# RTD_circuit.net
KiCad netlist of a schematic drawn in EAGLE
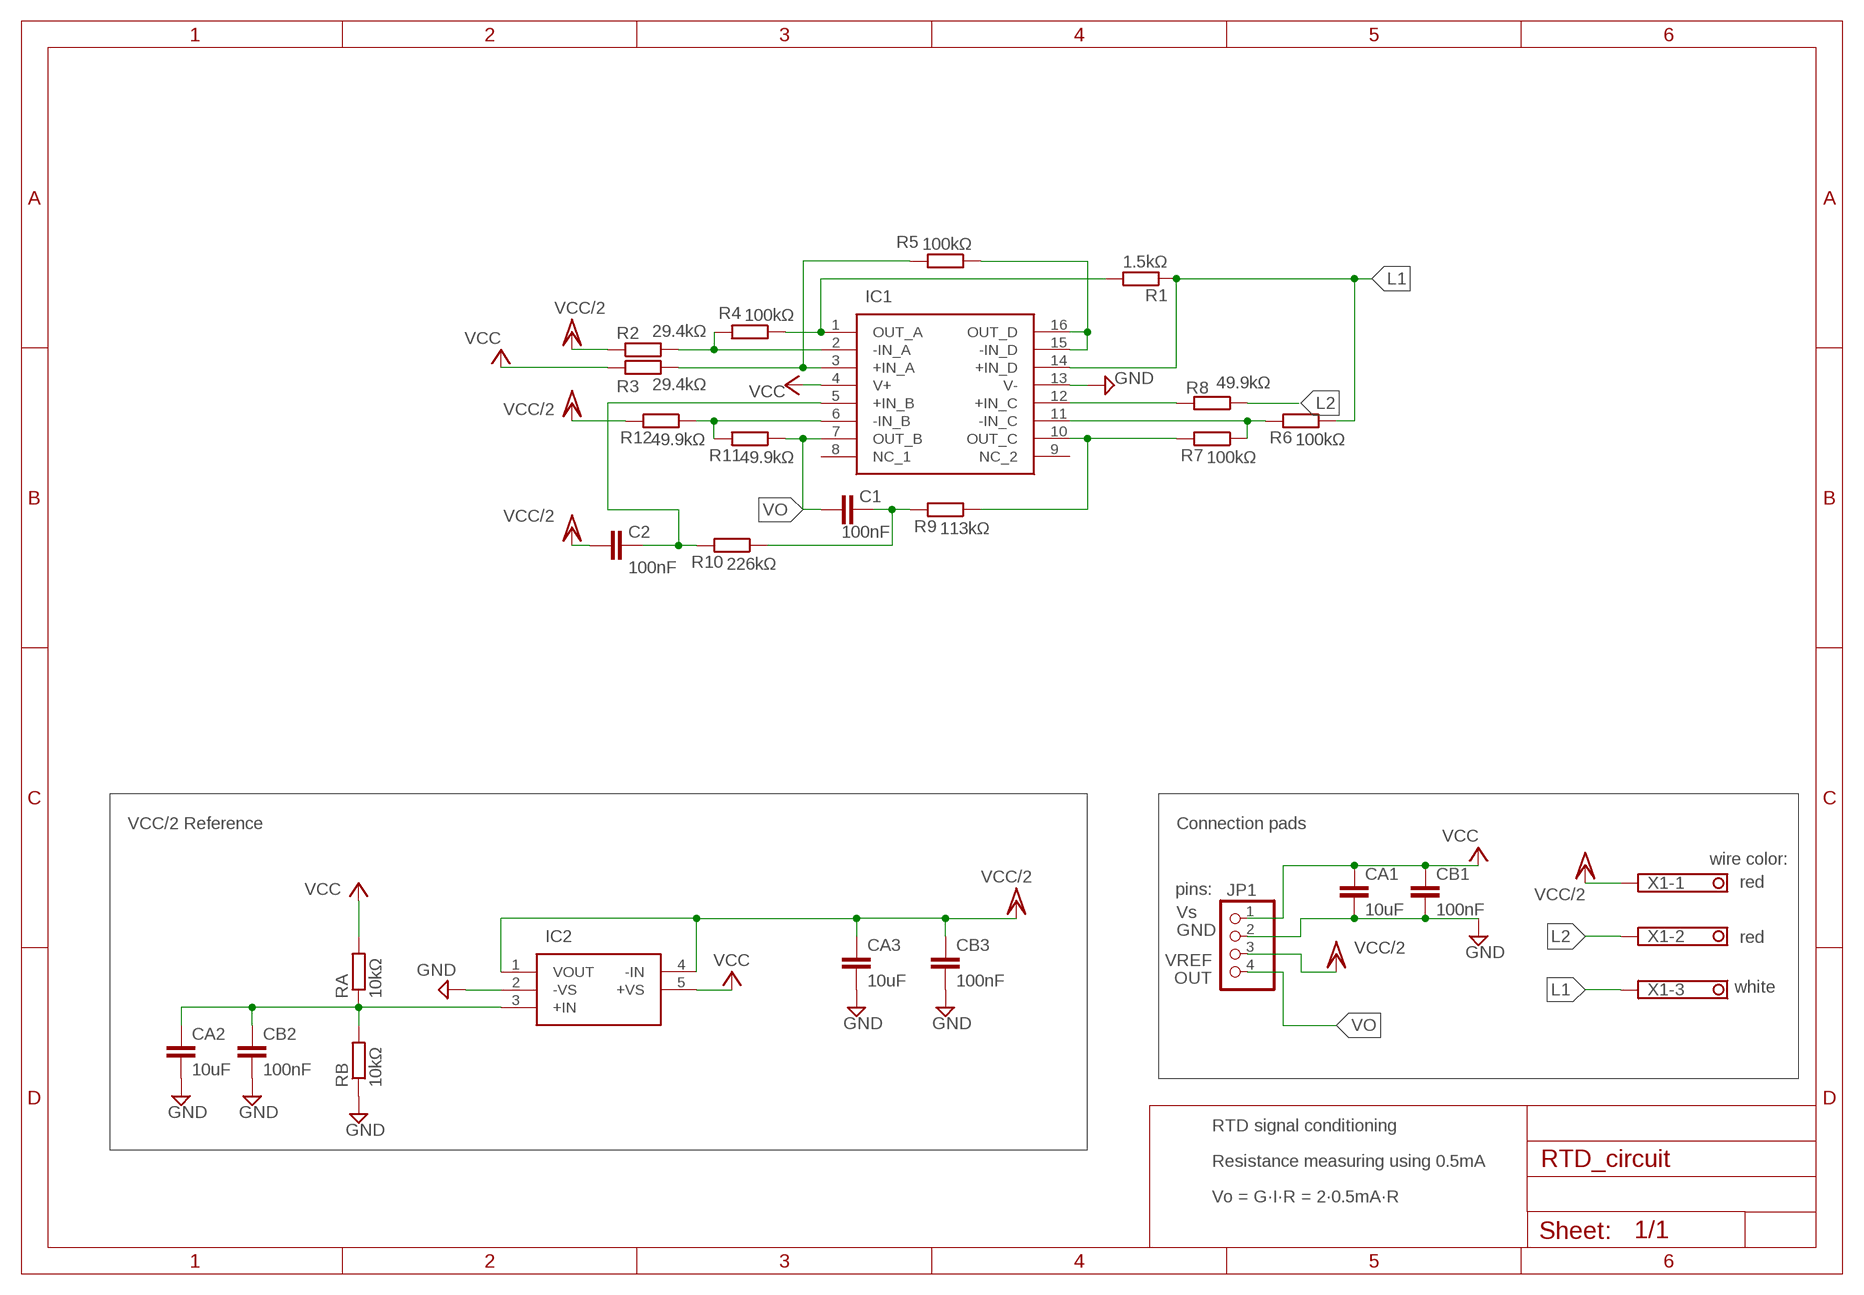
[diagram p0: schematic, sheet 1]

(export (version "E")
  (design (tool "Eeschema 10.0.6"))
  (components
    (comp (ref "C1")
      (value "100nF")
      (footprint "eagle-import:C0603")
      (libsource (lib "eagle-import") (part "C-EUC0603"))
    )
    (comp (ref "C2")
      (value "100nF")
      (footprint "eagle-import:C0603")
      (libsource (lib "eagle-import") (part "C-EUC0603"))
    )
    (comp (ref "CA1")
      (value "10uF")
      (footprint "eagle-import:C0603")
      (libsource (lib "eagle-import") (part "C-EUC0603"))
    )
    (comp (ref "CA2")
      (value "10uF")
      (footprint "eagle-import:C0603")
      (libsource (lib "eagle-import") (part "C-EUC0603"))
    )
    (comp (ref "CA3")
      (value "10uF")
      (footprint "eagle-import:C0603")
      (libsource (lib "eagle-import") (part "C-EUC0603"))
    )
    (comp (ref "CB1")
      (value "100nF")
      (footprint "eagle-import:C0603")
      (libsource (lib "eagle-import") (part "C-EUC0603"))
    )
    (comp (ref "CB2")
      (value "100nF")
      (footprint "eagle-import:C0603")
      (libsource (lib "eagle-import") (part "C-EUC0603"))
    )
    (comp (ref "CB3")
      (value "100nF")
      (footprint "eagle-import:C0603")
      (libsource (lib "eagle-import") (part "C-EUC0603"))
    )
    (comp (ref "IC1")
      (value "LT1079SW#PBF")
      (footprint "eagle-import:SOIC127P1032X264-16N")
      (fields (field (name "MOUSER_PART_NUMBER") "584-LT1079SW#PBF"))
      (libsource (lib "eagle-import") (part "LT1079SW#PBF"))
    )
    (comp (ref "IC2")
      (value "AD8031ARTZ-R2")
      (footprint "eagle-import:SOT95P280X145-5N")
      (fields (field (name "MOUSER_PART_NUMBER") "584-AD8031ARTZ-R2"))
      (libsource (lib "eagle-import") (part "AD8031ARTZ-R2"))
    )
    (comp (ref "JP1")
      (value "PINHD-1X4")
      (footprint "eagle-import:1X04")
      (libsource (lib "eagle-import") (part "PINHD-1X4"))
    )
    (comp (ref "R1")
      (value "1.5kΩ")
      (footprint "eagle-import:R0603")
      (libsource (lib "eagle-import") (part "R-EU_R0603"))
    )
    (comp (ref "R2")
      (value "29.4kΩ")
      (footprint "eagle-import:R0603")
      (libsource (lib "eagle-import") (part "R-EU_R0603"))
    )
    (comp (ref "R3")
      (value "29.4kΩ")
      (footprint "eagle-import:R0603")
      (libsource (lib "eagle-import") (part "R-EU_R0603"))
    )
    (comp (ref "R4")
      (value "100kΩ")
      (footprint "eagle-import:R0603")
      (libsource (lib "eagle-import") (part "R-EU_R0603"))
    )
    (comp (ref "R5")
      (value "100kΩ")
      (footprint "eagle-import:R0603")
      (libsource (lib "eagle-import") (part "R-EU_R0603"))
    )
    (comp (ref "R6")
      (value "100kΩ")
      (footprint "eagle-import:R0603")
      (libsource (lib "eagle-import") (part "R-EU_R0603"))
    )
    (comp (ref "R7")
      (value "100kΩ")
      (footprint "eagle-import:R0603")
      (libsource (lib "eagle-import") (part "R-EU_R0603"))
    )
    (comp (ref "R8")
      (value "49.9kΩ")
      (footprint "eagle-import:R0603")
      (libsource (lib "eagle-import") (part "R-EU_R0603"))
    )
    (comp (ref "R9")
      (value "113kΩ")
      (footprint "eagle-import:R0603")
      (libsource (lib "eagle-import") (part "R-EU_R0603"))
    )
    (comp (ref "R10")
      (value "226kΩ")
      (footprint "eagle-import:R0603")
      (libsource (lib "eagle-import") (part "R-EU_R0603"))
    )
    (comp (ref "R11")
      (value "49.9kΩ")
      (footprint "eagle-import:R0603")
      (libsource (lib "eagle-import") (part "R-EU_R0603"))
    )
    (comp (ref "R12")
      (value "49.9kΩ")
      (footprint "eagle-import:R0603")
      (libsource (lib "eagle-import") (part "R-EU_R0603"))
    )
    (comp (ref "RA")
      (value "10kΩ")
      (footprint "eagle-import:R0603")
      (libsource (lib "eagle-import") (part "R-EU_R0603"))
    )
    (comp (ref "RB")
      (value "10kΩ")
      (footprint "eagle-import:R0603")
      (libsource (lib "eagle-import") (part "R-EU_R0603"))
    )
    (comp (ref "X1")
      (value "1751251")
      (footprint "eagle-import:1751251")
      (libsource (lib "eagle-import") (part "1751251"))
    )
  )
  (nets
    (net (code "1") (name "GND") (class "Default")
      (node (ref "CA1") (pin "2") (pinfunction "2_2") (pintype "passive"))
      (node (ref "CA2") (pin "2") (pinfunction "2_2") (pintype "passive"))
      (node (ref "CA3") (pin "2") (pinfunction "2_2") (pintype "passive"))
      (node (ref "CB1") (pin "2") (pinfunction "2_2") (pintype "passive"))
      (node (ref "CB2") (pin "2") (pinfunction "2_2") (pintype "passive"))
      (node (ref "CB3") (pin "2") (pinfunction "2_2") (pintype "passive"))
      (node (ref "IC1") (pin "13") (pinfunction "V-_13") (pintype "bidirectional"))
      (node (ref "IC2") (pin "2") (pinfunction "-VS_2") (pintype "bidirectional"))
      (node (ref "JP1") (pin "2") (pinfunction "2_2") (pintype "passive"))
      (node (ref "RB") (pin "1") (pinfunction "1_1") (pintype "passive"))
    )
    (net (code "2") (name "L1") (class "Default")
      (node (ref "IC1") (pin "14") (pinfunction "+IN_D_14") (pintype "bidirectional"))
      (node (ref "R1") (pin "1") (pinfunction "1_1") (pintype "passive"))
      (node (ref "R6") (pin "1") (pinfunction "1_1") (pintype "passive"))
      (node (ref "X1") (pin "3") (pinfunction "K_3") (pintype "passive"))
    )
    (net (code "3") (name "L2") (class "Default")
      (node (ref "R8") (pin "1") (pinfunction "1_1") (pintype "passive"))
      (node (ref "X1") (pin "2") (pinfunction "K_2") (pintype "passive"))
    )
    (net (code "4") (name "Net-(C1-Pad1)") (class "Default")
      (node (ref "C1") (pin "1") (pinfunction "1_1") (pintype "passive"))
      (node (ref "R10") (pin "1") (pinfunction "1_1") (pintype "passive"))
      (node (ref "R9") (pin "2") (pinfunction "2_2") (pintype "passive"))
    )
    (net (code "5") (name "Net-(IC1-+IN_A)") (class "Default")
      (node (ref "IC1") (pin "3") (pinfunction "+IN_A_3") (pintype "bidirectional"))
      (node (ref "R3") (pin "2") (pinfunction "2_2") (pintype "passive"))
      (node (ref "R5") (pin "2") (pinfunction "2_2") (pintype "passive"))
    )
    (net (code "6") (name "Net-(IC1-+IN_B)") (class "Default")
      (node (ref "C2") (pin "1") (pinfunction "1_1") (pintype "passive"))
      (node (ref "IC1") (pin "5") (pinfunction "+IN_B_5") (pintype "bidirectional"))
      (node (ref "R10") (pin "2") (pinfunction "2_2") (pintype "passive"))
    )
    (net (code "7") (name "Net-(IC1-+IN_C)") (class "Default")
      (node (ref "IC1") (pin "12") (pinfunction "+IN_C_12") (pintype "bidirectional"))
      (node (ref "R8") (pin "2") (pinfunction "2_2") (pintype "passive"))
    )
    (net (code "8") (name "Net-(IC1--IN_A)") (class "Default")
      (node (ref "IC1") (pin "2") (pinfunction "-IN_A_2") (pintype "bidirectional"))
      (node (ref "R2") (pin "2") (pinfunction "2_2") (pintype "passive"))
      (node (ref "R4") (pin "2") (pinfunction "2_2") (pintype "passive"))
    )
    (net (code "9") (name "Net-(IC1--IN_B)") (class "Default")
      (node (ref "IC1") (pin "6") (pinfunction "-IN_B_6") (pintype "bidirectional"))
      (node (ref "R11") (pin "2") (pinfunction "2_2") (pintype "passive"))
      (node (ref "R12") (pin "1") (pinfunction "1_1") (pintype "passive"))
    )
    (net (code "10") (name "Net-(IC1--IN_C)") (class "Default")
      (node (ref "IC1") (pin "11") (pinfunction "-IN_C_11") (pintype "bidirectional"))
      (node (ref "R6") (pin "2") (pinfunction "2_2") (pintype "passive"))
      (node (ref "R7") (pin "1") (pinfunction "1_1") (pintype "passive"))
    )
    (net (code "11") (name "Net-(IC1--IN_D)") (class "Default")
      (node (ref "IC1") (pin "15") (pinfunction "-IN_D_15") (pintype "bidirectional"))
      (node (ref "IC1") (pin "16") (pinfunction "OUT_D_16") (pintype "bidirectional"))
      (node (ref "R5") (pin "1") (pinfunction "1_1") (pintype "passive"))
    )
    (net (code "12") (name "Net-(IC1-OUT_A)") (class "Default")
      (node (ref "IC1") (pin "1") (pinfunction "OUT_A_1") (pintype "bidirectional"))
      (node (ref "R1") (pin "2") (pinfunction "2_2") (pintype "passive"))
      (node (ref "R4") (pin "1") (pinfunction "1_1") (pintype "passive"))
    )
    (net (code "13") (name "Net-(IC1-OUT_C)") (class "Default")
      (node (ref "IC1") (pin "10") (pinfunction "OUT_C_10") (pintype "bidirectional"))
      (node (ref "R7") (pin "2") (pinfunction "2_2") (pintype "passive"))
      (node (ref "R9") (pin "1") (pinfunction "1_1") (pintype "passive"))
    )
    (net (code "14") (name "Net-(IC2-+IN)") (class "Default")
      (node (ref "CA2") (pin "1") (pinfunction "1_1") (pintype "passive"))
      (node (ref "CB2") (pin "1") (pinfunction "1_1") (pintype "passive"))
      (node (ref "IC2") (pin "3") (pinfunction "+IN_3") (pintype "bidirectional"))
      (node (ref "RA") (pin "1") (pinfunction "1_1") (pintype "passive"))
      (node (ref "RB") (pin "2") (pinfunction "2_2") (pintype "passive"))
    )
    (net (code "15") (name "VCC") (class "Default")
      (node (ref "CA1") (pin "1") (pinfunction "1_1") (pintype "passive"))
      (node (ref "CB1") (pin "1") (pinfunction "1_1") (pintype "passive"))
      (node (ref "IC1") (pin "4") (pinfunction "V+_4") (pintype "bidirectional"))
      (node (ref "IC2") (pin "5") (pinfunction "+VS_5") (pintype "bidirectional"))
      (node (ref "JP1") (pin "1") (pinfunction "1_1") (pintype "passive"))
      (node (ref "R3") (pin "1") (pinfunction "1_1") (pintype "passive"))
      (node (ref "RA") (pin "2") (pinfunction "2_2") (pintype "passive"))
    )
    (net (code "16") (name "VCC{slash}2") (class "Default")
      (node (ref "C2") (pin "2") (pinfunction "2_2") (pintype "passive"))
      (node (ref "CA3") (pin "1") (pinfunction "1_1") (pintype "passive"))
      (node (ref "CB3") (pin "1") (pinfunction "1_1") (pintype "passive"))
      (node (ref "IC2") (pin "1") (pinfunction "VOUT_1") (pintype "bidirectional"))
      (node (ref "IC2") (pin "4") (pinfunction "-IN_4") (pintype "bidirectional"))
      (node (ref "JP1") (pin "3") (pinfunction "3_3") (pintype "passive"))
      (node (ref "R12") (pin "2") (pinfunction "2_2") (pintype "passive"))
      (node (ref "R2") (pin "1") (pinfunction "1_1") (pintype "passive"))
      (node (ref "X1") (pin "1") (pinfunction "K_1") (pintype "passive"))
    )
    (net (code "17") (name "VO") (class "Default")
      (node (ref "C1") (pin "2") (pinfunction "2_2") (pintype "passive"))
      (node (ref "IC1") (pin "7") (pinfunction "OUT_B_7") (pintype "bidirectional"))
      (node (ref "JP1") (pin "4") (pinfunction "4_4") (pintype "passive"))
      (node (ref "R11") (pin "1") (pinfunction "1_1") (pintype "passive"))
    )
    (net (code "18") (name "unconnected-(IC1-NC_1-Pad8)") (class "Default")
      (node (ref "IC1") (pin "8") (pinfunction "NC_1_8") (pintype "bidirectional"))
    )
    (net (code "19") (name "unconnected-(IC1-NC_2-Pad9)") (class "Default")
      (node (ref "IC1") (pin "9") (pinfunction "NC_2_9") (pintype "bidirectional"))
    )
  )
)
